# Shield_schematic_v09b.net
KiCad netlist of a schematic drawn in EAGLE
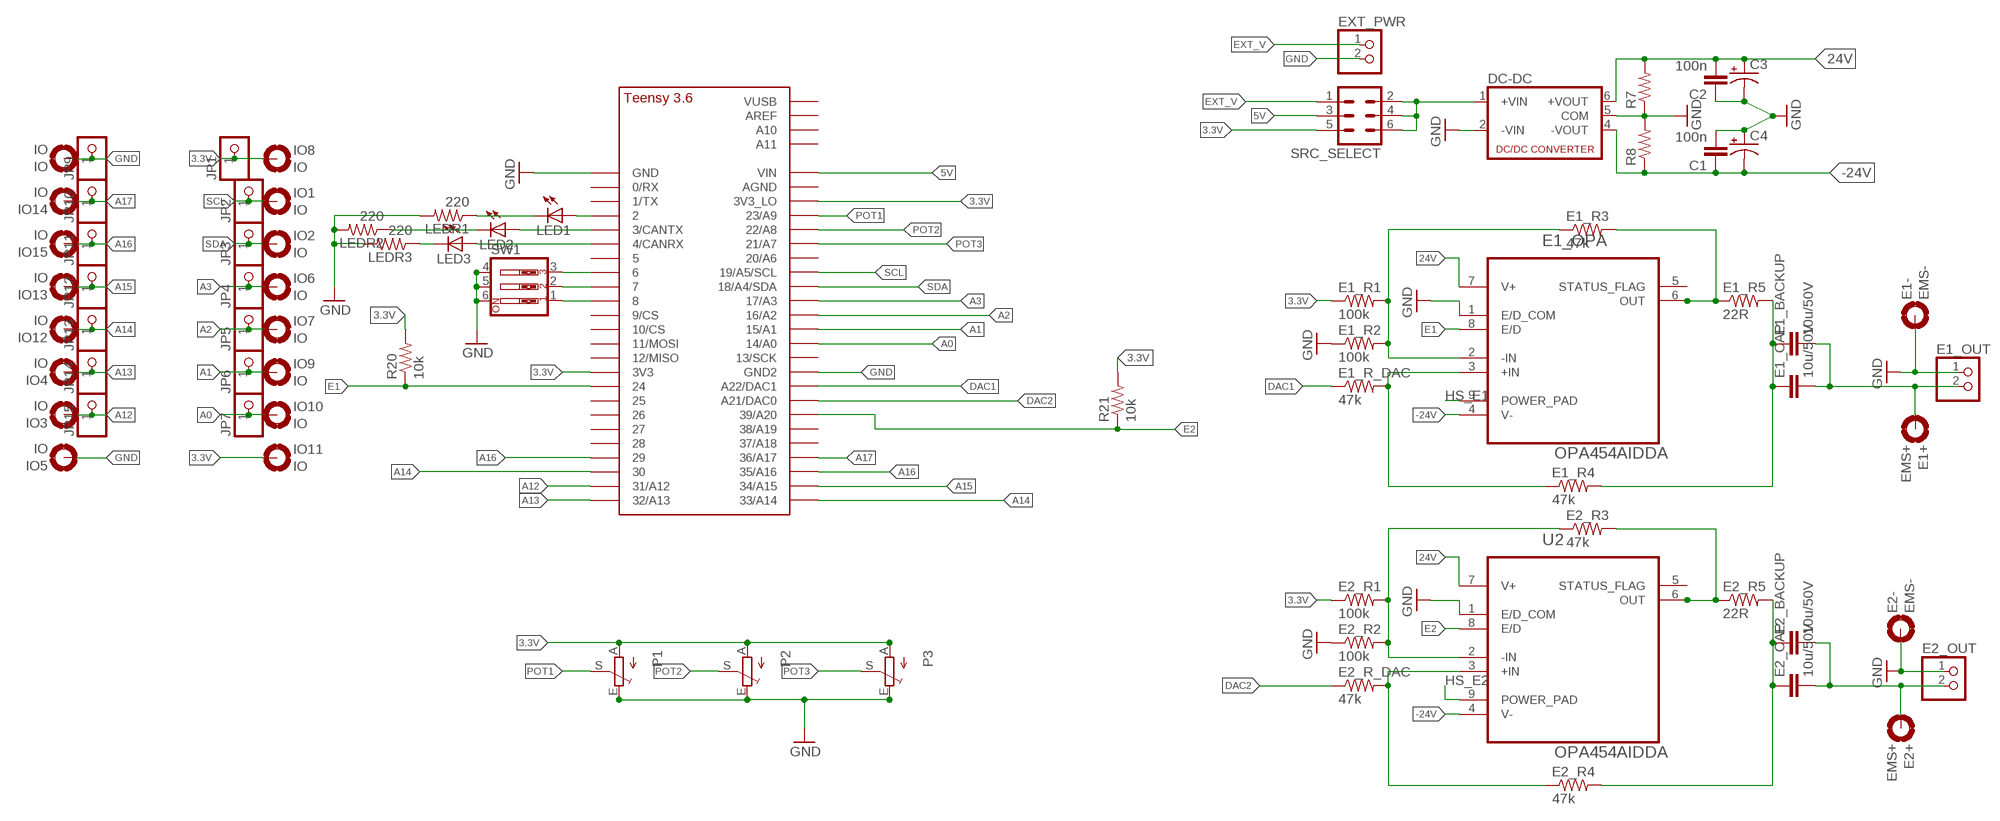
[diagram p0: schematic, sheet 1]

(export (version "E")
  (design (tool "Eeschema 10.0.6"))
  (components
    (comp (ref "C1")
      (value "100n")
      (footprint "eagle-import:1206")
      (libsource (lib "eagle-import") (part "CAP1206"))
    )
    (comp (ref "C2")
      (value "100n")
      (footprint "eagle-import:1206")
      (libsource (lib "eagle-import") (part "CAP1206"))
    )
    (comp (ref "C3")
      (value "CPOL-USE2.5-5")
      (footprint "eagle-import:E2,5-5")
      (libsource (lib "eagle-import") (part "CPOL-USE2.5-5"))
    )
    (comp (ref "C4")
      (value "CPOL-USE2.5-5")
      (footprint "eagle-import:E2,5-5")
      (libsource (lib "eagle-import") (part "CPOL-USE2.5-5"))
    )
    (comp (ref "DC-DC")
      (value "NMA")
      (footprint "eagle-import:NMA")
      (fields (field (name "MF") "C & D TECHNOLOGIES, INC") (field (name "MPN") "NMA0515SC"))
      (libsource (lib "eagle-import") (part "NMA"))
    )
    (comp (ref "E1+")
      (value "EMS+")
      (footprint "eagle-import:4,1-PAD")
      (libsource (lib "eagle-import") (part "MOUNT-PAD-ROUND4.1"))
    )
    (comp (ref "E1-")
      (value "EMS-")
      (footprint "eagle-import:4,1-PAD")
      (libsource (lib "eagle-import") (part "MOUNT-PAD-ROUND4.1"))
    )
    (comp (ref "E1_BACKUP")
      (value "10u/50V")
      (footprint "eagle-import:CAP-PTH-5MM")
      (libsource (lib "eagle-import") (part "CAPPTH1"))
    )
    (comp (ref "E1_CAP")
      (value "10u/50V")
      (footprint "eagle-import:1206")
      (libsource (lib "eagle-import") (part "CAP1206"))
    )
    (comp (ref "E1_OPA")
      (value "OPA454AIDDA")
      (footprint "eagle-import:SOIC127P600X170-9N")
      (libsource (lib "eagle-import") (part "OPA454AIDDA"))
    )
    (comp (ref "E1_OUT")
      (value "PINHD-1X2")
      (footprint "eagle-import:1X02")
      (libsource (lib "eagle-import") (part "PINHD-1X2"))
    )
    (comp (ref "E1_R1")
      (value "100k")
      (footprint "eagle-import:1206")
      (libsource (lib "eagle-import") (part "RESISTOR1206"))
    )
    (comp (ref "E1_R2")
      (value "100k")
      (footprint "eagle-import:1206")
      (libsource (lib "eagle-import") (part "RESISTOR1206"))
    )
    (comp (ref "E1_R3")
      (value "47k")
      (footprint "eagle-import:1206")
      (libsource (lib "eagle-import") (part "RESISTOR1206"))
    )
    (comp (ref "E1_R4")
      (value "47k")
      (footprint "eagle-import:1206")
      (libsource (lib "eagle-import") (part "RESISTOR1206"))
    )
    (comp (ref "E1_R5")
      (value "22R")
      (footprint "eagle-import:1206")
      (libsource (lib "eagle-import") (part "RESISTOR1206"))
    )
    (comp (ref "E1_R_DAC")
      (value "47k")
      (footprint "eagle-import:1206")
      (libsource (lib "eagle-import") (part "RESISTOR1206"))
    )
    (comp (ref "E2+")
      (value "EMS+")
      (footprint "eagle-import:4,1-PAD")
      (libsource (lib "eagle-import") (part "MOUNT-PAD-ROUND4.1"))
    )
    (comp (ref "E2-")
      (value "EMS-")
      (footprint "eagle-import:4,1-PAD")
      (libsource (lib "eagle-import") (part "MOUNT-PAD-ROUND4.1"))
    )
    (comp (ref "E2_BACKUP")
      (value "10u/50V")
      (footprint "eagle-import:CAP-PTH-5MM")
      (libsource (lib "eagle-import") (part "CAPPTH1"))
    )
    (comp (ref "E2_CAP")
      (value "10u/50V")
      (footprint "eagle-import:1206")
      (libsource (lib "eagle-import") (part "CAP1206"))
    )
    (comp (ref "E2_OUT")
      (value "PINHD-1X2")
      (footprint "eagle-import:1X02")
      (libsource (lib "eagle-import") (part "PINHD-1X2"))
    )
    (comp (ref "E2_R1")
      (value "100k")
      (footprint "eagle-import:1206")
      (libsource (lib "eagle-import") (part "RESISTOR1206"))
    )
    (comp (ref "E2_R2")
      (value "100k")
      (footprint "eagle-import:1206")
      (libsource (lib "eagle-import") (part "RESISTOR1206"))
    )
    (comp (ref "E2_R3")
      (value "47k")
      (footprint "eagle-import:1206")
      (libsource (lib "eagle-import") (part "RESISTOR1206"))
    )
    (comp (ref "E2_R4")
      (value "47k")
      (footprint "eagle-import:1206")
      (libsource (lib "eagle-import") (part "RESISTOR1206"))
    )
    (comp (ref "E2_R5")
      (value "22R")
      (footprint "eagle-import:1206")
      (libsource (lib "eagle-import") (part "RESISTOR1206"))
    )
    (comp (ref "E2_R_DAC")
      (value "47k")
      (footprint "eagle-import:1206")
      (libsource (lib "eagle-import") (part "RESISTOR1206"))
    )
    (comp (ref "EXT_PWR")
      (value "PINHD-1X2")
      (footprint "eagle-import:1X02")
      (libsource (lib "eagle-import") (part "PINHD-1X2"))
    )
    (comp (ref "IO")
      (value "IO")
      (footprint "eagle-import:2,8-PAD")
      (libsource (lib "eagle-import") (part "MOUNT-PAD-ROUND2.8"))
    )
    (comp (ref "IO1")
      (value "IO")
      (footprint "eagle-import:2,8-PAD")
      (libsource (lib "eagle-import") (part "MOUNT-PAD-ROUND2.8"))
    )
    (comp (ref "IO2")
      (value "IO")
      (footprint "eagle-import:2,8-PAD")
      (libsource (lib "eagle-import") (part "MOUNT-PAD-ROUND2.8"))
    )
    (comp (ref "IO3")
      (value "IO")
      (footprint "eagle-import:2,8-PAD")
      (libsource (lib "eagle-import") (part "MOUNT-PAD-ROUND2.8"))
    )
    (comp (ref "IO4")
      (value "IO")
      (footprint "eagle-import:2,8-PAD")
      (libsource (lib "eagle-import") (part "MOUNT-PAD-ROUND2.8"))
    )
    (comp (ref "IO5")
      (value "IO")
      (footprint "eagle-import:2,8-PAD")
      (libsource (lib "eagle-import") (part "MOUNT-PAD-ROUND2.8"))
    )
    (comp (ref "IO6")
      (value "IO")
      (footprint "eagle-import:2,8-PAD")
      (libsource (lib "eagle-import") (part "MOUNT-PAD-ROUND2.8"))
    )
    (comp (ref "IO7")
      (value "IO")
      (footprint "eagle-import:2,8-PAD")
      (libsource (lib "eagle-import") (part "MOUNT-PAD-ROUND2.8"))
    )
    (comp (ref "IO8")
      (value "IO")
      (footprint "eagle-import:2,8-PAD")
      (libsource (lib "eagle-import") (part "MOUNT-PAD-ROUND2.8"))
    )
    (comp (ref "IO9")
      (value "IO")
      (footprint "eagle-import:2,8-PAD")
      (libsource (lib "eagle-import") (part "MOUNT-PAD-ROUND2.8"))
    )
    (comp (ref "IO10")
      (value "IO")
      (footprint "eagle-import:2,8-PAD")
      (libsource (lib "eagle-import") (part "MOUNT-PAD-ROUND2.8"))
    )
    (comp (ref "IO11")
      (value "IO")
      (footprint "eagle-import:2,8-PAD")
      (libsource (lib "eagle-import") (part "MOUNT-PAD-ROUND2.8"))
    )
    (comp (ref "IO12")
      (value "IO")
      (footprint "eagle-import:2,8-PAD")
      (libsource (lib "eagle-import") (part "MOUNT-PAD-ROUND2.8"))
    )
    (comp (ref "IO13")
      (value "IO")
      (footprint "eagle-import:2,8-PAD")
      (libsource (lib "eagle-import") (part "MOUNT-PAD-ROUND2.8"))
    )
    (comp (ref "IO14")
      (value "IO")
      (footprint "eagle-import:2,8-PAD")
      (libsource (lib "eagle-import") (part "MOUNT-PAD-ROUND2.8"))
    )
    (comp (ref "IO15")
      (value "IO")
      (footprint "eagle-import:2,8-PAD")
      (libsource (lib "eagle-import") (part "MOUNT-PAD-ROUND2.8"))
    )
    (comp (ref "JP1")
      (value "PINHD-1X1")
      (footprint "eagle-import:1X01")
      (libsource (lib "eagle-import") (part "PINHD-1X1"))
    )
    (comp (ref "JP2")
      (value "PINHD-1X1")
      (footprint "eagle-import:1X01")
      (libsource (lib "eagle-import") (part "PINHD-1X1"))
    )
    (comp (ref "JP3")
      (value "PINHD-1X1")
      (footprint "eagle-import:1X01")
      (libsource (lib "eagle-import") (part "PINHD-1X1"))
    )
    (comp (ref "JP4")
      (value "PINHD-1X1")
      (footprint "eagle-import:1X01")
      (libsource (lib "eagle-import") (part "PINHD-1X1"))
    )
    (comp (ref "JP5")
      (value "PINHD-1X1")
      (footprint "eagle-import:1X01")
      (libsource (lib "eagle-import") (part "PINHD-1X1"))
    )
    (comp (ref "JP6")
      (value "PINHD-1X1")
      (footprint "eagle-import:1X01")
      (libsource (lib "eagle-import") (part "PINHD-1X1"))
    )
    (comp (ref "JP7")
      (value "PINHD-1X1")
      (footprint "eagle-import:1X01")
      (libsource (lib "eagle-import") (part "PINHD-1X1"))
    )
    (comp (ref "JP9")
      (value "PINHD-1X1")
      (footprint "eagle-import:1X01")
      (libsource (lib "eagle-import") (part "PINHD-1X1"))
    )
    (comp (ref "JP10")
      (value "PINHD-1X1")
      (footprint "eagle-import:1X01")
      (libsource (lib "eagle-import") (part "PINHD-1X1"))
    )
    (comp (ref "JP11")
      (value "PINHD-1X1")
      (footprint "eagle-import:1X01")
      (libsource (lib "eagle-import") (part "PINHD-1X1"))
    )
    (comp (ref "JP12")
      (value "PINHD-1X1")
      (footprint "eagle-import:1X01")
      (libsource (lib "eagle-import") (part "PINHD-1X1"))
    )
    (comp (ref "JP13")
      (value "PINHD-1X1")
      (footprint "eagle-import:1X01")
      (libsource (lib "eagle-import") (part "PINHD-1X1"))
    )
    (comp (ref "JP14")
      (value "PINHD-1X1")
      (footprint "eagle-import:1X01")
      (libsource (lib "eagle-import") (part "PINHD-1X1"))
    )
    (comp (ref "JP15")
      (value "PINHD-1X1")
      (footprint "eagle-import:1X01")
      (libsource (lib "eagle-import") (part "PINHD-1X1"))
    )
    (comp (ref "LED1")
      (value "LEDCHIPLED_0805")
      (footprint "eagle-import:CHIPLED_0805")
      (libsource (lib "eagle-import") (part "LEDCHIPLED_0805"))
    )
    (comp (ref "LED2")
      (value "LEDCHIPLED_0805")
      (footprint "eagle-import:CHIPLED_0805")
      (libsource (lib "eagle-import") (part "LEDCHIPLED_0805"))
    )
    (comp (ref "LED3")
      (value "LEDCHIPLED_0805")
      (footprint "eagle-import:CHIPLED_0805")
      (libsource (lib "eagle-import") (part "LEDCHIPLED_0805"))
    )
    (comp (ref "LEDR1")
      (value "220")
      (footprint "eagle-import:1206")
      (libsource (lib "eagle-import") (part "RESISTOR1206"))
    )
    (comp (ref "LEDR2")
      (value "220")
      (footprint "eagle-import:1206")
      (libsource (lib "eagle-import") (part "RESISTOR1206"))
    )
    (comp (ref "LEDR3")
      (value "220")
      (footprint "eagle-import:1206")
      (libsource (lib "eagle-import") (part "RESISTOR1206"))
    )
    (comp (ref "P1")
      (value "TRIM_EU-B25P")
      (footprint "eagle-import:B25P")
      (libsource (lib "eagle-import") (part "TRIM_EU-B25P"))
    )
    (comp (ref "P2")
      (value "TRIM_EU-B25P")
      (footprint "eagle-import:B25P")
      (libsource (lib "eagle-import") (part "TRIM_EU-B25P"))
    )
    (comp (ref "P3")
      (value "TRIM_EU-B25P")
      (footprint "eagle-import:B25P")
      (libsource (lib "eagle-import") (part "TRIM_EU-B25P"))
    )
    (comp (ref "R7")
      (value "RESISTORKIT")
      (footprint "eagle-import:AXIAL-0.3-KIT")
      (libsource (lib "eagle-import") (part "RESISTORKIT"))
    )
    (comp (ref "R8")
      (value "RESISTORKIT")
      (footprint "eagle-import:AXIAL-0.3-KIT")
      (libsource (lib "eagle-import") (part "RESISTORKIT"))
    )
    (comp (ref "R20")
      (value "10k")
      (footprint "eagle-import:1206")
      (libsource (lib "eagle-import") (part "RESISTOR1206"))
    )
    (comp (ref "R21")
      (value "10k")
      (footprint "eagle-import:1206")
      (libsource (lib "eagle-import") (part "RESISTOR1206"))
    )
    (comp (ref "SRC_SELECT")
      (value "MA03-2")
      (footprint "eagle-import:MA03-2")
      (libsource (lib "eagle-import") (part "MA03-2"))
    )
    (comp (ref "SW1")
      (value "SW_DIP-3")
      (footprint "eagle-import:EDG-03")
      (libsource (lib "eagle-import") (part "SW_DIP-3"))
    )
    (comp (ref "U$1")
      (value "TEENSY_3.5/3.6_BASIC")
      (footprint "eagle-import:TEENSY_3.5_3.6_BASIC")
      (libsource (lib "eagle-import") (part "TEENSY_3.5/3.6_BASIC"))
    )
    (comp (ref "U2")
      (value "OPA454AIDDA")
      (footprint "eagle-import:SOIC127P600X170-9N")
      (libsource (lib "eagle-import") (part "OPA454AIDDA"))
    )
  )
  (nets
    (net (code "1") (name "-24V") (class "Default")
      (node (ref "C1") (pin "1") (pinfunction "1_1") (pintype "passive"))
      (node (ref "C4") (pin "-") (pinfunction "-_-") (pintype "passive"))
      (node (ref "DC-DC") (pin "4") (pinfunction "-VOUT_4") (pintype "passive"))
      (node (ref "E1_OPA") (pin "4") (pinfunction "V-_4") (pintype "power_in"))
      (node (ref "R8") (pin "P$1") (pinfunction "1_P$1") (pintype "passive"))
      (node (ref "U2") (pin "4") (pinfunction "V-_4") (pintype "power_in"))
    )
    (net (code "2") (name "/HS_E1") (class "Default")
      (node (ref "E1_OPA") (pin "9") (pinfunction "POWER_PAD_9") (pintype "passive"))
    )
    (net (code "3") (name "/HS_E2") (class "Default")
      (node (ref "U2") (pin "9") (pinfunction "POWER_PAD_9") (pintype "passive"))
    )
    (net (code "4") (name "3.3V") (class "Default")
      (node (ref "E1_R1") (pin "1") (pinfunction "1_1") (pintype "passive"))
      (node (ref "E2_R1") (pin "1") (pinfunction "1_1") (pintype "passive"))
      (node (ref "IO11") (pin "B2,8") (pinfunction "MOUNT_B2,8") (pintype "passive"))
      (node (ref "IO8") (pin "B2,8") (pinfunction "MOUNT_B2,8") (pintype "passive"))
      (node (ref "JP1") (pin "1") (pinfunction "1_1") (pintype "passive"))
      (node (ref "P1") (pin "A") (pinfunction "A_A") (pintype "passive"))
      (node (ref "P2") (pin "A") (pinfunction "A_A") (pintype "passive"))
      (node (ref "P3") (pin "A") (pinfunction "A_A") (pintype "passive"))
      (node (ref "R20") (pin "2") (pinfunction "2_2") (pintype "passive"))
      (node (ref "R21") (pin "2") (pinfunction "2_2") (pintype "passive"))
      (node (ref "SRC_SELECT") (pin "5") (pinfunction "5_5") (pintype "passive"))
      (node (ref "U$1") (pin "3V3") (pinfunction "3V3_3V3") (pintype "bidirectional"))
      (node (ref "U$1") (pin "3V3_LO") (pinfunction "3V3_LO_3V3_LO") (pintype "bidirectional"))
    )
    (net (code "5") (name "5V") (class "Default")
      (node (ref "SRC_SELECT") (pin "3") (pinfunction "3_3") (pintype "passive"))
      (node (ref "U$1") (pin "VIN") (pinfunction "VIN_VIN") (pintype "bidirectional"))
    )
    (net (code "6") (name "24V") (class "Default")
      (node (ref "C2") (pin "2") (pinfunction "2_2") (pintype "passive"))
      (node (ref "C3") (pin "+") (pinfunction "+_+") (pintype "passive"))
      (node (ref "DC-DC") (pin "6") (pinfunction "+VOUT_6") (pintype "passive"))
      (node (ref "E1_OPA") (pin "7") (pinfunction "V+_7") (pintype "power_in"))
      (node (ref "R7") (pin "P$2") (pinfunction "2_P$2") (pintype "passive"))
      (node (ref "U2") (pin "7") (pinfunction "V+_7") (pintype "power_in"))
    )
    (net (code "7") (name "A0") (class "Default")
      (node (ref "IO10") (pin "B2,8") (pinfunction "MOUNT_B2,8") (pintype "passive"))
      (node (ref "JP7") (pin "1") (pinfunction "1_1") (pintype "passive"))
      (node (ref "U$1") (pin "14/A0") (pinfunction "14/A0_14/A0") (pintype "bidirectional"))
    )
    (net (code "8") (name "A1") (class "Default")
      (node (ref "IO9") (pin "B2,8") (pinfunction "MOUNT_B2,8") (pintype "passive"))
      (node (ref "JP6") (pin "1") (pinfunction "1_1") (pintype "passive"))
      (node (ref "U$1") (pin "15/A1") (pinfunction "15/A1_15/A1") (pintype "bidirectional"))
    )
    (net (code "9") (name "A2") (class "Default")
      (node (ref "IO7") (pin "B2,8") (pinfunction "MOUNT_B2,8") (pintype "passive"))
      (node (ref "JP5") (pin "1") (pinfunction "1_1") (pintype "passive"))
      (node (ref "U$1") (pin "16/A2") (pinfunction "16/A2_16/A2") (pintype "bidirectional"))
    )
    (net (code "10") (name "A3") (class "Default")
      (node (ref "IO6") (pin "B2,8") (pinfunction "MOUNT_B2,8") (pintype "passive"))
      (node (ref "JP4") (pin "1") (pinfunction "1_1") (pintype "passive"))
      (node (ref "U$1") (pin "17/A3") (pinfunction "17/A3_17/A3") (pintype "bidirectional"))
    )
    (net (code "11") (name "A12") (class "Default")
      (node (ref "IO3") (pin "B2,8") (pinfunction "MOUNT_B2,8") (pintype "passive"))
      (node (ref "JP15") (pin "1") (pinfunction "1_1") (pintype "passive"))
      (node (ref "U$1") (pin "31/A12") (pinfunction "31/A12_31/A12") (pintype "bidirectional"))
    )
    (net (code "12") (name "A13") (class "Default")
      (node (ref "IO4") (pin "B2,8") (pinfunction "MOUNT_B2,8") (pintype "passive"))
      (node (ref "JP14") (pin "1") (pinfunction "1_1") (pintype "passive"))
      (node (ref "U$1") (pin "32/A13") (pinfunction "32/A13_32/A13") (pintype "bidirectional"))
    )
    (net (code "13") (name "A14") (class "Default")
      (node (ref "IO12") (pin "B2,8") (pinfunction "MOUNT_B2,8") (pintype "passive"))
      (node (ref "JP13") (pin "1") (pinfunction "1_1") (pintype "passive"))
      (node (ref "U$1") (pin "30") (pinfunction "30_30") (pintype "bidirectional"))
      (node (ref "U$1") (pin "33/A14") (pinfunction "33/A14_33/A14") (pintype "bidirectional"))
    )
    (net (code "14") (name "A15") (class "Default")
      (node (ref "IO13") (pin "B2,8") (pinfunction "MOUNT_B2,8") (pintype "passive"))
      (node (ref "JP12") (pin "1") (pinfunction "1_1") (pintype "passive"))
      (node (ref "U$1") (pin "34/A15") (pinfunction "34/A15_34/A15") (pintype "bidirectional"))
    )
    (net (code "15") (name "A16") (class "Default")
      (node (ref "IO15") (pin "B2,8") (pinfunction "MOUNT_B2,8") (pintype "passive"))
      (node (ref "JP11") (pin "1") (pinfunction "1_1") (pintype "passive"))
      (node (ref "U$1") (pin "29") (pinfunction "29_29") (pintype "bidirectional"))
      (node (ref "U$1") (pin "35/A16") (pinfunction "35/A16_35/A16") (pintype "bidirectional"))
    )
    (net (code "16") (name "A17") (class "Default")
      (node (ref "IO14") (pin "B2,8") (pinfunction "MOUNT_B2,8") (pintype "passive"))
      (node (ref "JP10") (pin "1") (pinfunction "1_1") (pintype "passive"))
      (node (ref "U$1") (pin "36/A17") (pinfunction "36/A17_36/A17") (pintype "bidirectional"))
    )
    (net (code "17") (name "DAC1") (class "Default")
      (node (ref "E1_R_DAC") (pin "1") (pinfunction "1_1") (pintype "passive"))
      (node (ref "U$1") (pin "A22/DAC1") (pinfunction "A22/DAC1_A22/DAC1") (pintype "bidirectional"))
    )
    (net (code "18") (name "DAC2") (class "Default")
      (node (ref "E2_R_DAC") (pin "1") (pinfunction "1_1") (pintype "passive"))
      (node (ref "U$1") (pin "21/DAC0") (pinfunction "A21/DAC0_21/DAC0") (pintype "bidirectional"))
    )
    (net (code "19") (name "E1") (class "Default")
      (node (ref "E1_OPA") (pin "8") (pinfunction "E/D_8") (pintype "input"))
      (node (ref "R20") (pin "1") (pinfunction "1_1") (pintype "passive"))
      (node (ref "U$1") (pin "24") (pinfunction "24_24") (pintype "bidirectional"))
    )
    (net (code "20") (name "E2") (class "Default")
      (node (ref "R21") (pin "1") (pinfunction "1_1") (pintype "passive"))
      (node (ref "U$1") (pin "39/A20") (pinfunction "39/A20_39/A20") (pintype "bidirectional"))
      (node (ref "U2") (pin "8") (pinfunction "E/D_8") (pintype "input"))
    )
    (net (code "21") (name "EXT_V") (class "Default")
      (node (ref "EXT_PWR") (pin "1") (pinfunction "1_1") (pintype "passive"))
      (node (ref "SRC_SELECT") (pin "1") (pinfunction "1_1") (pintype "passive"))
    )
    (net (code "22") (name "GND") (class "Default")
      (node (ref "C1") (pin "2") (pinfunction "2_2") (pintype "passive"))
      (node (ref "C2") (pin "1") (pinfunction "1_1") (pintype "passive"))
      (node (ref "C3") (pin "-") (pinfunction "-_-") (pintype "passive"))
      (node (ref "C4") (pin "+") (pinfunction "+_+") (pintype "passive"))
      (node (ref "DC-DC") (pin "2") (pinfunction "-VIN_2") (pintype "passive"))
      (node (ref "DC-DC") (pin "5") (pinfunction "COM_5") (pintype "passive"))
      (node (ref "E1-") (pin "B4,1") (pinfunction "MOUNT_B4,1") (pintype "passive"))
      (node (ref "E1_OPA") (pin "1") (pinfunction "E/D_COM_1") (pintype "input"))
      (node (ref "E1_OUT") (pin "1") (pinfunction "1_1") (pintype "passive"))
      (node (ref "E1_R2") (pin "1") (pinfunction "1_1") (pintype "passive"))
      (node (ref "E2-") (pin "B4,1") (pinfunction "MOUNT_B4,1") (pintype "passive"))
      (node (ref "E2_OUT") (pin "1") (pinfunction "1_1") (pintype "passive"))
      (node (ref "E2_R2") (pin "1") (pinfunction "1_1") (pintype "passive"))
      (node (ref "EXT_PWR") (pin "2") (pinfunction "2_2") (pintype "passive"))
      (node (ref "IO") (pin "B2,8") (pinfunction "MOUNT_B2,8") (pintype "passive"))
      (node (ref "IO5") (pin "B2,8") (pinfunction "MOUNT_B2,8") (pintype "passive"))
      (node (ref "JP9") (pin "1") (pinfunction "1_1") (pintype "passive"))
      (node (ref "LEDR1") (pin "2") (pinfunction "2_2") (pintype "passive"))
      (node (ref "LEDR2") (pin "2") (pinfunction "2_2") (pintype "passive"))
      (node (ref "LEDR3") (pin "2") (pinfunction "2_2") (pintype "passive"))
      (node (ref "P1") (pin "E") (pinfunction "E_E") (pintype "passive"))
      (node (ref "P2") (pin "E") (pinfunction "E_E") (pintype "passive"))
      (node (ref "P3") (pin "E") (pinfunction "E_E") (pintype "passive"))
      (node (ref "R7") (pin "P$1") (pinfunction "1_P$1") (pintype "passive"))
      (node (ref "R8") (pin "P$2") (pinfunction "2_P$2") (pintype "passive"))
      (node (ref "SW1") (pin "4") (pinfunction "4_4") (pintype "passive"))
      (node (ref "SW1") (pin "5") (pinfunction "5_5") (pintype "passive"))
      (node (ref "SW1") (pin "6") (pinfunction "6_6") (pintype "passive"))
      (node (ref "U$1") (pin "GND") (pinfunction "GND_GND") (pintype "bidirectional"))
      (node (ref "U$1") (pin "GND2") (pinfunction "GND2_GND2") (pintype "bidirectional"))
      (node (ref "U2") (pin "1") (pinfunction "E/D_COM_1") (pintype "input"))
    )
    (net (code "23") (name "Net-(DC-DC-+VIN)") (class "Default")
      (node (ref "DC-DC") (pin "1") (pinfunction "+VIN_1") (pintype "passive"))
      (node (ref "SRC_SELECT") (pin "2") (pinfunction "2_2") (pintype "passive"))
      (node (ref "SRC_SELECT") (pin "4") (pinfunction "4_4") (pintype "passive"))
      (node (ref "SRC_SELECT") (pin "6") (pinfunction "6_6") (pintype "passive"))
    )
    (net (code "24") (name "Net-(E1+-MOUNT)") (class "Default")
      (node (ref "E1+") (pin "B4,1") (pinfunction "MOUNT_B4,1") (pintype "passive"))
      (node (ref "E1_BACKUP") (pin "2") (pinfunction "2_2") (pintype "passive"))
      (node (ref "E1_CAP") (pin "2") (pinfunction "2_2") (pintype "passive"))
      (node (ref "E1_OUT") (pin "2") (pinfunction "2_2") (pintype "passive"))
    )
    (net (code "25") (name "Net-(E1_BACKUP-Pad1)") (class "Default")
      (node (ref "E1_BACKUP") (pin "1") (pinfunction "1_1") (pintype "passive"))
      (node (ref "E1_CAP") (pin "1") (pinfunction "1_1") (pintype "passive"))
      (node (ref "E1_R4") (pin "2") (pinfunction "2_2") (pintype "passive"))
      (node (ref "E1_R5") (pin "2") (pinfunction "2_2") (pintype "passive"))
    )
    (net (code "26") (name "Net-(E1_OPA-+IN)") (class "Default")
      (node (ref "E1_OPA") (pin "3") (pinfunction "+IN_3") (pintype "input"))
      (node (ref "E1_R4") (pin "1") (pinfunction "1_1") (pintype "passive"))
      (node (ref "E1_R_DAC") (pin "2") (pinfunction "2_2") (pintype "passive"))
    )
    (net (code "27") (name "Net-(E1_OPA--IN)") (class "Default")
      (node (ref "E1_OPA") (pin "2") (pinfunction "-IN_2") (pintype "input"))
      (node (ref "E1_R1") (pin "2") (pinfunction "2_2") (pintype "passive"))
      (node (ref "E1_R2") (pin "2") (pinfunction "2_2") (pintype "passive"))
      (node (ref "E1_R3") (pin "1") (pinfunction "1_1") (pintype "passive"))
    )
    (net (code "28") (name "Net-(E1_OPA-OUT)") (class "Default")
      (node (ref "E1_OPA") (pin "6") (pinfunction "OUT_6") (pintype "output"))
      (node (ref "E1_R3") (pin "2") (pinfunction "2_2") (pintype "passive"))
      (node (ref "E1_R5") (pin "1") (pinfunction "1_1") (pintype "passive"))
    )
    (net (code "29") (name "Net-(E2+-MOUNT)") (class "Default")
      (node (ref "E2+") (pin "B4,1") (pinfunction "MOUNT_B4,1") (pintype "passive"))
      (node (ref "E2_BACKUP") (pin "2") (pinfunction "2_2") (pintype "passive"))
      (node (ref "E2_CAP") (pin "2") (pinfunction "2_2") (pintype "passive"))
      (node (ref "E2_OUT") (pin "2") (pinfunction "2_2") (pintype "passive"))
    )
    (net (code "30") (name "Net-(E2_BACKUP-Pad1)") (class "Default")
      (node (ref "E2_BACKUP") (pin "1") (pinfunction "1_1") (pintype "passive"))
      (node (ref "E2_CAP") (pin "1") (pinfunction "1_1") (pintype "passive"))
      (node (ref "E2_R4") (pin "2") (pinfunction "2_2") (pintype "passive"))
      (node (ref "E2_R5") (pin "2") (pinfunction "2_2") (pintype "passive"))
    )
    (net (code "31") (name "Net-(LED1-PadA)") (class "Default")
      (node (ref "LED1") (pin "A") (pinfunction "A_A") (pintype "passive"))
      (node (ref "U$1") (pin "2") (pinfunction "2_2") (pintype "bidirectional"))
    )
    (net (code "32") (name "Net-(LED1-PadC)") (class "Default")
      (node (ref "LED1") (pin "C") (pinfunction "C_C") (pintype "passive"))
      (node (ref "LEDR1") (pin "1") (pinfunction "1_1") (pintype "passive"))
    )
    (net (code "33") (name "Net-(LED2-PadA)") (class "Default")
      (node (ref "LED2") (pin "A") (pinfunction "A_A") (pintype "passive"))
      (node (ref "U$1") (pin "3/CANTX") (pinfunction "3/CANTX_3/CANTX") (pintype "bidirectional"))
    )
    (net (code "34") (name "Net-(LED2-PadC)") (class "Default")
      (node (ref "LED2") (pin "C") (pinfunction "C_C") (pintype "passive"))
      (node (ref "LEDR2") (pin "1") (pinfunction "1_1") (pintype "passive"))
    )
    (net (code "35") (name "Net-(LED3-PadA)") (class "Default")
      (node (ref "LED3") (pin "A") (pinfunction "A_A") (pintype "passive"))
      (node (ref "U$1") (pin "4/CANRX") (pinfunction "4/CANRX_4/CANRX") (pintype "bidirectional"))
    )
    (net (code "36") (name "Net-(LED3-PadC)") (class "Default")
      (node (ref "LED3") (pin "C") (pinfunction "C_C") (pintype "passive"))
      (node (ref "LEDR3") (pin "1") (pinfunction "1_1") (pintype "passive"))
    )
    (net (code "37") (name "Net-(SW1-Pad1)") (class "Default")
      (node (ref "SW1") (pin "1") (pinfunction "1_1") (pintype "passive"))
      (node (ref "U$1") (pin "8") (pinfunction "8_8") (pintype "bidirectional"))
    )
    (net (code "38") (name "Net-(SW1-Pad2)") (class "Default")
      (node (ref "SW1") (pin "2") (pinfunction "2_2") (pintype "passive"))
      (node (ref "U$1") (pin "7") (pinfunction "7_7") (pintype "bidirectional"))
    )
    (net (code "39") (name "Net-(SW1-Pad3)") (class "Default")
      (node (ref "SW1") (pin "3") (pinfunction "3_3") (pintype "passive"))
      (node (ref "U$1") (pin "6") (pinfunction "6_6") (pintype "bidirectional"))
    )
    (net (code "40") (name "Net-(U2-+IN)") (class "Default")
      (node (ref "E2_R4") (pin "1") (pinfunction "1_1") (pintype "passive"))
      (node (ref "E2_R_DAC") (pin "2") (pinfunction "2_2") (pintype "passive"))
      (node (ref "U2") (pin "3") (pinfunction "+IN_3") (pintype "input"))
    )
    (net (code "41") (name "Net-(U2--IN)") (class "Default")
      (node (ref "E2_R1") (pin "2") (pinfunction "2_2") (pintype "passive"))
      (node (ref "E2_R2") (pin "2") (pinfunction "2_2") (pintype "passive"))
      (node (ref "E2_R3") (pin "1") (pinfunction "1_1") (pintype "passive"))
      (node (ref "U2") (pin "2") (pinfunction "-IN_2") (pintype "input"))
    )
    (net (code "42") (name "Net-(U2-OUT)") (class "Default")
      (node (ref "E2_R3") (pin "2") (pinfunction "2_2") (pintype "passive"))
      (node (ref "E2_R5") (pin "1") (pinfunction "1_1") (pintype "passive"))
      (node (ref "U2") (pin "6") (pinfunction "OUT_6") (pintype "output"))
    )
    (net (code "43") (name "POT1") (class "Default")
      (node (ref "P1") (pin "S") (pinfunction "S_S") (pintype "passive"))
      (node (ref "U$1") (pin "23/A9") (pinfunction "23/A9_23/A9") (pintype "bidirectional"))
    )
    (net (code "44") (name "POT2") (class "Default")
      (node (ref "P2") (pin "S") (pinfunction "S_S") (pintype "passive"))
      (node (ref "U$1") (pin "22/A8") (pinfunction "22/A8_22/A8") (pintype "bidirectional"))
    )
    (net (code "45") (name "POT3") (class "Default")
      (node (ref "P3") (pin "S") (pinfunction "S_S") (pintype "passive"))
      (node (ref "U$1") (pin "21/A7") (pinfunction "21/A7_21/A7") (pintype "bidirectional"))
    )
    (net (code "46") (name "SCL") (class "Default")
      (node (ref "IO1") (pin "B2,8") (pinfunction "MOUNT_B2,8") (pintype "passive"))
      (node (ref "JP2") (pin "1") (pinfunction "1_1") (pintype "passive"))
      (node (ref "U$1") (pin "19/A5/SCL") (pinfunction "19/A5/SCL_19/A5/SCL") (pintype "bidirectional"))
    )
    (net (code "47") (name "SDA") (class "Default")
      (node (ref "IO2") (pin "B2,8") (pinfunction "MOUNT_B2,8") (pintype "passive"))
      (node (ref "JP3") (pin "1") (pinfunction "1_1") (pintype "passive"))
      (node (ref "U$1") (pin "18/A4/SDA") (pinfunction "18/A4/SDA_18/A4/SDA") (pintype "bidirectional"))
    )
    (net (code "48") (name "unconnected-(E1_OPA-STATUS_FLAG-Pad5)") (class "Default")
      (node (ref "E1_OPA") (pin "5") (pinfunction "STATUS_FLAG_5") (pintype "output"))
    )
    (net (code "49") (name "unconnected-(U$1-Pad0{slash}RX)") (class "Default")
      (node (ref "U$1") (pin "0/RX") (pinfunction "0/RX_0/RX") (pintype "bidirectional"))
    )
    (net (code "50") (name "unconnected-(U$1-Pad1{slash}TX)") (class "Default")
      (node (ref "U$1") (pin "1/TX") (pinfunction "1/TX_1/TX") (pintype "bidirectional"))
    )
    (net (code "51") (name "unconnected-(U$1-Pad5)") (class "Default")
      (node (ref "U$1") (pin "5") (pinfunction "5_5") (pintype "bidirectional"))
    )
    (net (code "52") (name "unconnected-(U$1-Pad9{slash}CS)") (class "Default")
      (node (ref "U$1") (pin "9/CS") (pinfunction "9/CS_9/CS") (pintype "bidirectional"))
    )
    (net (code "53") (name "unconnected-(U$1-Pad10{slash}CS)") (class "Default")
      (node (ref "U$1") (pin "10/CS") (pinfunction "10/CS_10/CS") (pintype "bidirectional"))
    )
    (net (code "54") (name "unconnected-(U$1-Pad11{slash}MOSI)") (class "Default")
      (node (ref "U$1") (pin "11/MOSI") (pinfunction "11/MOSI_11/MOSI") (pintype "bidirectional"))
    )
    (net (code "55") (name "unconnected-(U$1-Pad12{slash}MISO)") (class "Default")
      (node (ref "U$1") (pin "12/MISO") (pinfunction "12/MISO_12/MISO") (pintype "bidirectional"))
    )
    (net (code "56") (name "unconnected-(U$1-Pad13{slash}SCK)") (class "Default")
      (node (ref "U$1") (pin "13/SCK") (pinfunction "13/SCK_13/SCK") (pintype "bidirectional"))
    )
    (net (code "57") (name "unconnected-(U$1-Pad20{slash}A6)") (class "Default")
      (node (ref "U$1") (pin "20/A6") (pinfunction "20/A6_20/A6") (pintype "bidirectional"))
    )
    (net (code "58") (name "unconnected-(U$1-Pad25)") (class "Default")
      (node (ref "U$1") (pin "25") (pinfunction "25_25") (pintype "bidirectional"))
    )
    (net (code "59") (name "unconnected-(U$1-Pad26)") (class "Default")
      (node (ref "U$1") (pin "26") (pinfunction "26_26") (pintype "bidirectional"))
    )
    (net (code "60") (name "unconnected-(U$1-Pad27)") (class "Default")
      (node (ref "U$1") (pin "27") (pinfunction "27_27") (pintype "bidirectional"))
    )
    (net (code "61") (name "unconnected-(U$1-Pad28)") (class "Default")
      (node (ref "U$1") (pin "28") (pinfunction "28_28") (pintype "bidirectional"))
    )
    (net (code "62") (name "unconnected-(U$1-Pad37{slash}A18)") (class "Default")
      (node (ref "U$1") (pin "37/A18") (pinfunction "37/A18_37/A18") (pintype "bidirectional"))
    )
    (net (code "63") (name "unconnected-(U$1-Pad38{slash}A19)") (class "Default")
      (node (ref "U$1") (pin "38/A19") (pinfunction "38/A19_38/A19") (pintype "bidirectional"))
    )
    (net (code "64") (name "unconnected-(U$1-PadA10)") (class "Default")
      (node (ref "U$1") (pin "A10") (pinfunction "A10_A10") (pintype "bidirectional"))
    )
    (net (code "65") (name "unconnected-(U$1-PadA11)") (class "Default")
      (node (ref "U$1") (pin "A11") (pinfunction "A11_A11") (pintype "bidirectional"))
    )
    (net (code "66") (name "unconnected-(U$1-PadAGND)") (class "Default")
      (node (ref "U$1") (pin "AGND") (pinfunction "AGND_AGND") (pintype "bidirectional"))
    )
    (net (code "67") (name "unconnected-(U$1-PadAREF)") (class "Default")
      (node (ref "U$1") (pin "AREF") (pinfunction "AREF_AREF") (pintype "bidirectional"))
    )
    (net (code "68") (name "unconnected-(U$1-PadVUSB)") (class "Default")
      (node (ref "U$1") (pin "VUSB") (pinfunction "VUSB_VUSB") (pintype "bidirectional"))
    )
    (net (code "69") (name "unconnected-(U2-STATUS_FLAG-Pad5)") (class "Default")
      (node (ref "U2") (pin "5") (pinfunction "STATUS_FLAG_5") (pintype "output"))
    )
  )
)
